# HBridge_Top_Level.net
KiCad netlist of a schematic drawn in Altium Designer
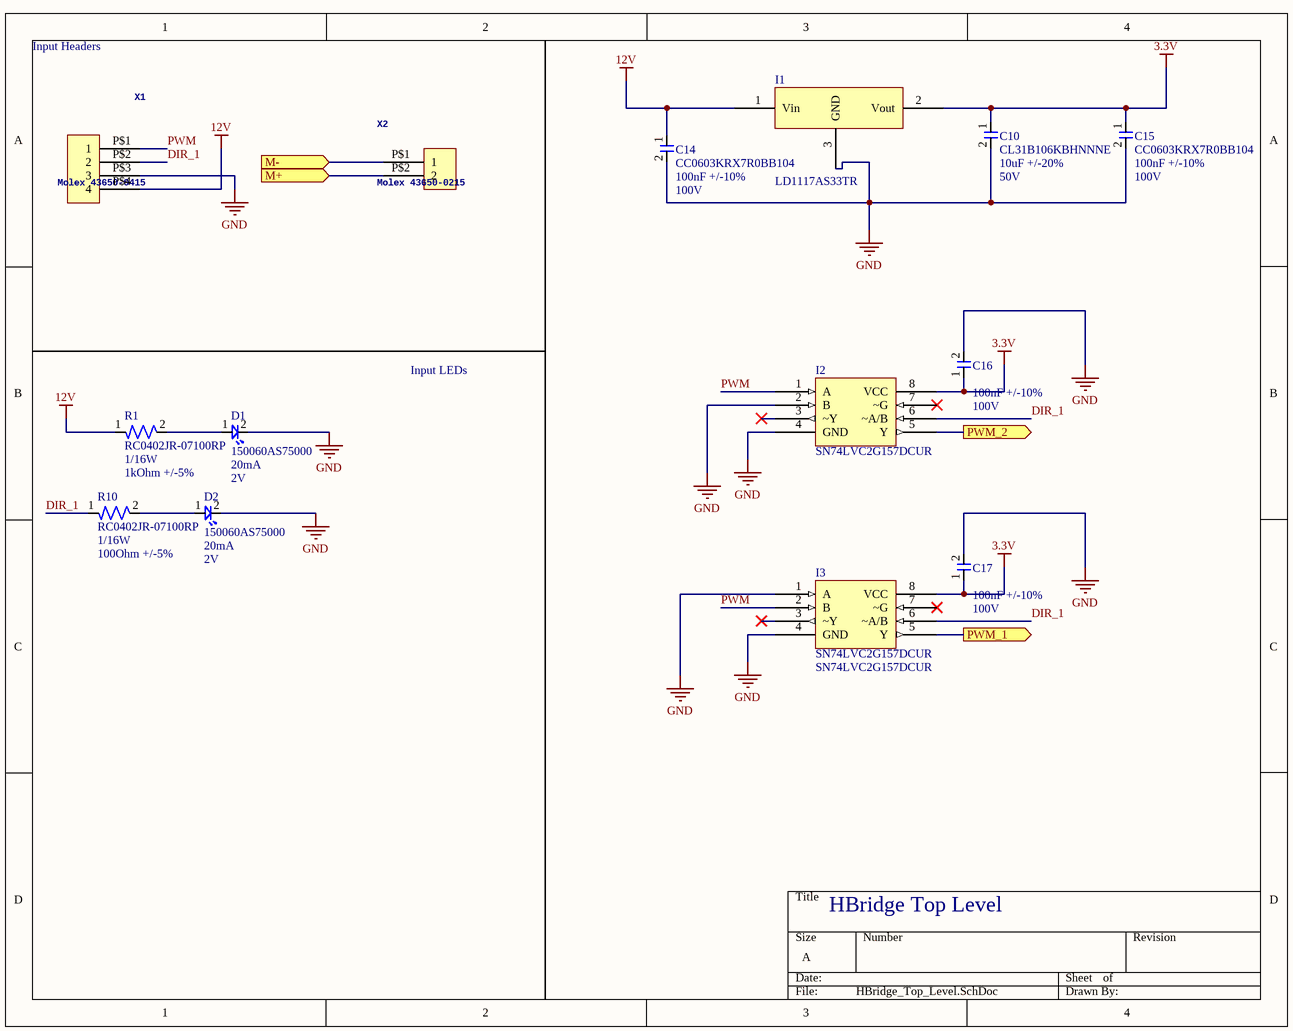
[diagram p0: HBridge_Top_Level.SchDoc]

(export (version "E")
  (design (tool "Eeschema 10.0.6"))
  (components
    (comp (ref "C10")
      (value "CL31B106KBHNNNE")
      (footprint "CAP-1206")
      (description "10 µF ±10% 50V Ceramic Capacitor X7R 1206 (3216 Metric)")
      (fields
        (field (name "MANUFACTURER") "Samsung Electro-Mechanics")
        (field (name "CAPACITANCE") "10uF +/-20%")
        (field (name "VOLTAGE RATING") "50V")
      )
      (libsource (lib "MasterLib") (part "CAP-10U-0001"))
    )
    (comp (ref "C14")
      (value "CC0603KRX7R0BB104")
      (footprint "CAP-0603")
      (description "CAP CER 0.1UF 100V X7R 0603")
      (fields
        (field (name "MANUFACTURER") "YAGEO")
        (field (name "CAPACITANCE") "100nF +/-10%")
        (field (name "VOLTAGE RATING") "100V")
      )
      (libsource (lib "MasterLib") (part "CAP-100N-0001"))
    )
    (comp (ref "C15")
      (value "CC0603KRX7R0BB104")
      (footprint "CAP-0603")
      (description "CAP CER 0.1UF 100V X7R 0603")
      (fields
        (field (name "MANUFACTURER") "YAGEO")
        (field (name "CAPACITANCE") "100nF +/-10%")
        (field (name "VOLTAGE RATING") "100V")
      )
      (libsource (lib "MasterLib") (part "CAP-100N-0001"))
    )
    (comp (ref "C16")
      (value "CC0603KRX7R0BB104")
      (footprint "CAP-0603")
      (description "CAP CER 0.1UF 100V X7R 0603")
      (fields
        (field (name "MANUFACTURER") "YAGEO")
        (field (name "CAPACITANCE") "100nF +/-10%")
        (field (name "VOLTAGE RATING") "100V")
      )
      (libsource (lib "MasterLib") (part "CAP-100N-0001"))
    )
    (comp (ref "C17")
      (value "CC0603KRX7R0BB104")
      (footprint "CAP-0603")
      (description "CAP CER 0.1UF 100V X7R 0603")
      (fields
        (field (name "MANUFACTURER") "YAGEO")
        (field (name "CAPACITANCE") "100nF +/-10%")
        (field (name "VOLTAGE RATING") "100V")
      )
      (libsource (lib "MasterLib") (part "CAP-100N-0001"))
    )
    (comp (ref "D1")
      (value "150060AS75000")
      (footprint "LED-0603")
      (description "CAP CER 0.1UF 100V X7R 0603")
      (fields
        (field (name "MANUFACTURER") "Wurth Electronik")
        (field (name "CURRENT RATING") "20mA")
        (field (name "VF") "2V")
      )
      (libsource (lib "MasterLib") (part "LED_Amber_0001"))
    )
    (comp (ref "D2")
      (value "150060AS75000")
      (footprint "LED-0603")
      (description "CAP CER 0.1UF 100V X7R 0603")
      (fields
        (field (name "MANUFACTURER") "Wurth Electronik")
        (field (name "CURRENT RATING") "20mA")
        (field (name "VF") "2V")
      )
      (libsource (lib "MasterLib") (part "LED_Amber_0001"))
    )
    (comp (ref "I1")
      (value "LD1117AS33TR")
      (footprint "IC-SOT-223")
      (description "Linear Voltage Regulator IC Positive Fixed 1 Output 1A SOT-223")
      (fields (field (name "MANUFACTURER PART NUMBER") "LD1117AS33TR"))
      (libsource (lib "MasterLib") (part "IC-LDO-0001"))
    )
    (comp (ref "I2")
      (value "SN74LVC2G157DCUR")
      (footprint "IC-MUX-8VSSOP")
      (libsource (lib "MasterLib") (part "IC-MUX-0001"))
    )
    (comp (ref "I3")
      (value "SN74LVC2G157DCUR")
      (footprint "IC-MUX-8VSSOP")
      (description "Multiplexer 1 x 2:1 8-VSSOP")
      (fields (field (name "MANUFACTURER PART NUMBER") "SN74LVC2G157DCUR"))
      (libsource (lib "MasterLib") (part "IC-MUX-0001"))
    )
    (comp (ref "R1")
      (value "RC0402JR-07100RP")
      (footprint "RES-0402")
      (description "RES SMD 1K OHM 5% 1/16W 0402")
      (fields
        (field (name "MANUFACTURER PART NUMBER") "RC0402JR-071KP")
        (field (name "MANUFACTURER") "YAGEO")
        (field (name "POWER RATING") "1/16W")
        (field (name "RESISTANCE") "1kOhm +/-5%")
      )
      (libsource (lib "MasterLib") (part "RES-1K-0001"))
    )
    (comp (ref "R10")
      (value "RC0402JR-07100RP")
      (footprint "RES-0402")
      (description "RES SMD 100 OHM 5% 1/16W 0402")
      (fields
        (field (name "MANUFACTURER") "YAGEO")
        (field (name "POWER RATING") "1/16W")
        (field (name "RESISTANCE") "100Ohm +/-5%")
      )
      (libsource (lib "MasterLib") (part "RES-100-0001"))
    )
    (comp (ref "X1")
      (value "Molex 43650-0415")
      (footprint "43650-0415")
      (libsource (lib "Molex Microfit") (part "Micro-Fit Molex 4 Pin Vertical"))
    )
    (comp (ref "X2")
      (value "Molex 43650-0215")
      (footprint "43650-0215")
      (libsource (lib "Molex Microfit") (part "Micro-Fit Molex 2 Pin Vertical"))
    )
  )
  (nets
    (net (code "1") (name "/DIR_1") (class "Default")
      (node (ref "I2") (pin "6") (pinfunction "~A/B_6") (pintype "input"))
      (node (ref "I3") (pin "6") (pinfunction "~A/B_6") (pintype "input"))
      (node (ref "R10") (pin "1") (pinfunction "1_1") (pintype "passive"))
      (node (ref "X1") (pin "P$2") (pinfunction "2_P$2") (pintype "passive"))
    )
    (net (code "2") (name "/M+") (class "Default")
      (node (ref "X2") (pin "P$2") (pinfunction "2_P$2") (pintype "passive"))
    )
    (net (code "3") (name "/M-") (class "Default")
      (node (ref "X2") (pin "P$1") (pinfunction "1_P$1") (pintype "passive"))
    )
    (net (code "4") (name "/PWM") (class "Default")
      (node (ref "I2") (pin "1") (pinfunction "A_1") (pintype "input"))
      (node (ref "I3") (pin "2") (pinfunction "B_2") (pintype "input"))
      (node (ref "X1") (pin "P$1") (pinfunction "1_P$1") (pintype "passive"))
    )
    (net (code "5") (name "/PWM_1") (class "Default")
      (node (ref "I3") (pin "5") (pinfunction "Y_5") (pintype "output"))
    )
    (net (code "6") (name "/PWM_2") (class "Default")
      (node (ref "I2") (pin "5") (pinfunction "Y_5") (pintype "output"))
    )
    (net (code "7") (name "3.3V") (class "Default")
      (node (ref "C10") (pin "1") (pinfunction "1_1") (pintype "passive"))
      (node (ref "C15") (pin "1") (pinfunction "1_1") (pintype "passive"))
      (node (ref "C16") (pin "1") (pinfunction "1_1") (pintype "passive"))
      (node (ref "C17") (pin "1") (pinfunction "1_1") (pintype "passive"))
      (node (ref "I1") (pin "2") (pinfunction "Vout_2") (pintype "power_in"))
      (node (ref "I2") (pin "8") (pinfunction "VCC_8") (pintype "power_in"))
      (node (ref "I3") (pin "8") (pinfunction "VCC_8") (pintype "power_in"))
    )
    (net (code "8") (name "12V") (class "Default")
      (node (ref "C14") (pin "1") (pinfunction "1_1") (pintype "passive"))
      (node (ref "I1") (pin "1") (pinfunction "Vin_1") (pintype "power_in"))
      (node (ref "R1") (pin "1") (pinfunction "1_1") (pintype "passive"))
      (node (ref "X1") (pin "P$4") (pinfunction "4_P$4") (pintype "passive"))
    )
    (net (code "9") (name "GND") (class "Default")
      (node (ref "C10") (pin "2") (pinfunction "2_2") (pintype "passive"))
      (node (ref "C14") (pin "2") (pinfunction "2_2") (pintype "passive"))
      (node (ref "C15") (pin "2") (pinfunction "2_2") (pintype "passive"))
      (node (ref "C16") (pin "2") (pinfunction "2_2") (pintype "passive"))
      (node (ref "C17") (pin "2") (pinfunction "2_2") (pintype "passive"))
      (node (ref "D1") (pin "2") (pinfunction "2_2") (pintype "passive"))
      (node (ref "D2") (pin "2") (pinfunction "2_2") (pintype "passive"))
      (node (ref "I1") (pin "3") (pinfunction "GND_3") (pintype "power_in"))
      (node (ref "I2") (pin "2") (pinfunction "B_2") (pintype "input"))
      (node (ref "I2") (pin "4") (pinfunction "GND_4") (pintype "power_in"))
      (node (ref "I3") (pin "1") (pinfunction "A_1") (pintype "input"))
      (node (ref "I3") (pin "4") (pinfunction "GND_4") (pintype "power_in"))
      (node (ref "X1") (pin "P$3") (pinfunction "3_P$3") (pintype "passive"))
    )
    (net (code "10") (name "Net-(D1-Pad1)") (class "Default")
      (node (ref "D1") (pin "1") (pinfunction "1_1") (pintype "passive"))
      (node (ref "R1") (pin "2") (pinfunction "2_2") (pintype "passive"))
    )
    (net (code "11") (name "Net-(D2-Pad1)") (class "Default")
      (node (ref "D2") (pin "1") (pinfunction "1_1") (pintype "passive"))
      (node (ref "R10") (pin "2") (pinfunction "2_2") (pintype "passive"))
    )
    (net (code "12") (name "unconnected-(I2-~G-Pad7)") (class "Default")
      (node (ref "I2") (pin "7") (pinfunction "~G_7") (pintype "input+no_connect"))
    )
    (net (code "13") (name "unconnected-(I2-~Y-Pad3)") (class "Default")
      (node (ref "I2") (pin "3") (pinfunction "~Y_3") (pintype "output+no_connect"))
    )
    (net (code "14") (name "unconnected-(I3-~G-Pad7)") (class "Default")
      (node (ref "I3") (pin "7") (pinfunction "~G_7") (pintype "input+no_connect"))
    )
    (net (code "15") (name "unconnected-(I3-~Y-Pad3)") (class "Default")
      (node (ref "I3") (pin "3") (pinfunction "~Y_3") (pintype "output+no_connect"))
    )
  )
)
